# CATS-GS-GNSS.net
KiCad netlist of a schematic drawn in Altium Designer
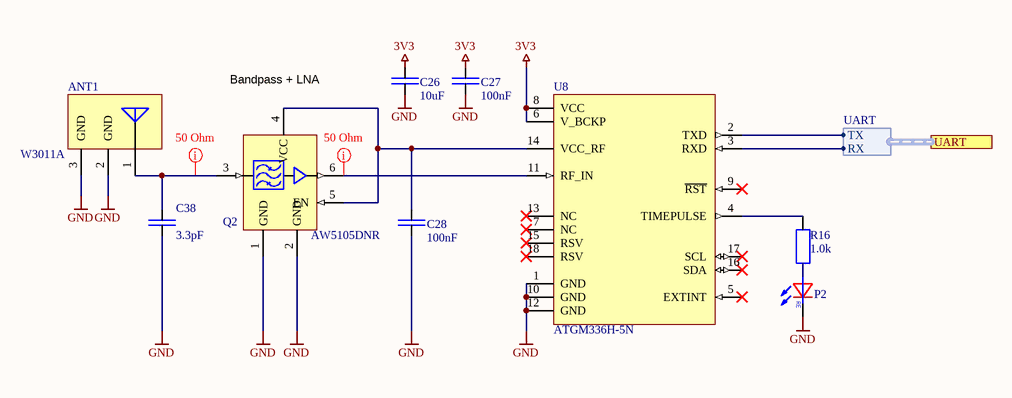
[diagram p0: CATS-GS-GNSS.SchDoc]

(export (version "E")
  (design (tool "Eeschema 10.0.6"))
  (components
    (comp (ref "ANT1")
      (value "W3011A")
      (footprint "SMD Antenna W3011A")
      (description "RF ANT 1.575GHZ CHIP SOLDER SMD")
      (libsource (lib "RF") (part "W3011A"))
    )
    (comp (ref "C26")
      (value "10uF")
      (footprint "SMD Keramikkondensator 0603")
      (description "SMD Ceramic Capacitor E6")
      (libsource (lib "Ceramic Capacitors-E6") (part "E6 - 10uF"))
    )
    (comp (ref "C27")
      (value "100nF")
      (footprint "SMD Keramikkondensator 0402")
      (description "SMD Ceramic Capacitor E6")
      (libsource (lib "CATS-EUROC") (part "E6 - 100nF"))
    )
    (comp (ref "C28")
      (value "100nF")
      (footprint "SMD Keramikkondensator 0402")
      (description "SMD Ceramic Capacitor E6")
      (libsource (lib "CATS-EUROC") (part "E6 - 100nF"))
    )
    (comp (ref "C38")
      (value "3.3pF")
      (footprint "SMD Keramikkondensator 0402")
      (description "SMD Ceramic Capacitor E6")
      (libsource (lib "Ceramic Capacitors-E6") (part "E6 - 3.3nF"))
    )
    (comp (ref "P2")
      (value "LED")
      (footprint "SMD LED 0603")
      (description "Color LED")
      (libsource (lib "Diodes") (part "LED"))
    )
    (comp (ref "Q2")
      (value "AW5105DNR")
      (footprint "SMD LNA AW5105DNR")
      (description "BDS/GPS/GNSS INTEGRATED FRONT-END MODULE WITH\r\nLOW NOISE AMPLIFIER AND FILTER")
      (libsource (lib "Analog") (part "AW5105DNR"))
    )
    (comp (ref "R16")
      (value "1.0k")
      (footprint "SMD Widerstand 0402")
      (description "SMD Chip Resistor E24")
      (libsource (lib "CATS-EUROC") (part "E24 - 1.0k"))
    )
    (comp (ref "U8")
      (value "ATGM336H-5N")
      (footprint "SMD MAX-8")
      (description "Chinese Crap GNSS Module")
      (libsource (lib "Sensors") (part "ATGM336H-5N"))
    )
  )
  (nets
    (net (code "2") (name "/RX") (class "Default")
      (node (ref "U8") (pin "3") (pinfunction "RXD_3") (pintype "input"))
    )
    (net (code "3") (name "/TX") (class "Default")
      (node (ref "U8") (pin "2") (pinfunction "TXD_2") (pintype "output"))
    )
    (net (code "5") (name "3V3") (class "Default")
      (node (ref "C26") (pin "2") (pinfunction "2_2") (pintype "passive"))
      (node (ref "C27") (pin "2") (pinfunction "2_2") (pintype "passive"))
      (node (ref "U8") (pin "6") (pinfunction "V_BCKP_6") (pintype "passive"))
      (node (ref "U8") (pin "8") (pinfunction "VCC_8") (pintype "passive"))
    )
    (net (code "6") (name "GND") (class "Default")
      (node (ref "ANT1") (pin "2") (pinfunction "GND_2") (pintype "passive"))
      (node (ref "ANT1") (pin "3") (pinfunction "GND_3") (pintype "passive"))
      (node (ref "C26") (pin "1") (pinfunction "1_1") (pintype "passive"))
      (node (ref "C27") (pin "1") (pinfunction "1_1") (pintype "passive"))
      (node (ref "C28") (pin "1") (pinfunction "1_1") (pintype "passive"))
      (node (ref "C38") (pin "1") (pinfunction "1_1") (pintype "passive"))
      (node (ref "P2") (pin "K") (pinfunction "K_K") (pintype "passive"))
      (node (ref "Q2") (pin "1") (pinfunction "GND_1") (pintype "passive"))
      (node (ref "Q2") (pin "2") (pinfunction "GND_2") (pintype "passive"))
      (node (ref "U8") (pin "1") (pinfunction "GND_1") (pintype "passive"))
      (node (ref "U8") (pin "10") (pinfunction "GND_10") (pintype "passive"))
      (node (ref "U8") (pin "12") (pinfunction "GND_12") (pintype "passive"))
    )
    (net (code "7") (name "Net-(ANT1-Pad1)_1") (class "Default")
      (node (ref "ANT1") (pin "1") (pinfunction "1_1") (pintype "passive"))
      (node (ref "C38") (pin "2") (pinfunction "2_2") (pintype "passive"))
      (node (ref "Q2") (pin "3") (pinfunction "3_3") (pintype "input"))
    )
    (net (code "8") (name "Net-(P2-PadA)") (class "Default")
      (node (ref "P2") (pin "A") (pinfunction "A_A") (pintype "passive"))
      (node (ref "R16") (pin "1") (pinfunction "1_1") (pintype "passive"))
    )
    (net (code "9") (name "Net-(Q2-VCC)") (class "Default")
      (node (ref "C28") (pin "2") (pinfunction "2_2") (pintype "passive"))
      (node (ref "Q2") (pin "4") (pinfunction "VCC_4") (pintype "passive"))
      (node (ref "Q2") (pin "5") (pinfunction "EN_5") (pintype "input"))
      (node (ref "U8") (pin "14") (pinfunction "VCC_RF_14") (pintype "passive"))
    )
    (net (code "10") (name "Net-(U8-RF_IN)") (class "Default")
      (node (ref "Q2") (pin "6") (pinfunction "EN_6") (pintype "output"))
      (node (ref "U8") (pin "11") (pinfunction "RF_IN_11") (pintype "input"))
    )
    (net (code "11") (name "Net-(U8-TIMEPULSE)") (class "Default")
      (node (ref "R16") (pin "2") (pinfunction "2_2") (pintype "passive"))
      (node (ref "U8") (pin "4") (pinfunction "TIMEPULSE_4") (pintype "output"))
    )
    (net (code "12") (name "unconnected-(ANT1-Pad1)") (class "Default")
      (node (ref "ANT1") (pin "1") (pinfunction "1_1") (pintype "passive"))
    )
    (net (code "13") (name "unconnected-(U8-EXTINT-Pad5)") (class "Default")
      (node (ref "U8") (pin "5") (pinfunction "EXTINT_5") (pintype "input+no_connect"))
    )
    (net (code "14") (name "unconnected-(U8-NC-Pad7)") (class "Default")
      (node (ref "U8") (pin "7") (pinfunction "NC_7") (pintype "passive+no_connect"))
    )
    (net (code "15") (name "unconnected-(U8-NC-Pad13)") (class "Default")
      (node (ref "U8") (pin "13") (pinfunction "NC_13") (pintype "passive+no_connect"))
    )
    (net (code "16") (name "unconnected-(U8-RSV-Pad15)") (class "Default")
      (node (ref "U8") (pin "15") (pinfunction "RSV_15") (pintype "passive+no_connect"))
    )
    (net (code "17") (name "unconnected-(U8-RSV-Pad18)") (class "Default")
      (node (ref "U8") (pin "18") (pinfunction "RSV_18") (pintype "passive+no_connect"))
    )
    (net (code "18") (name "unconnected-(U8-SCL-Pad17)") (class "Default")
      (node (ref "U8") (pin "17") (pinfunction "SCL_17") (pintype "bidirectional+no_connect"))
    )
    (net (code "19") (name "unconnected-(U8-SDA-Pad16)") (class "Default")
      (node (ref "U8") (pin "16") (pinfunction "SDA_16") (pintype "bidirectional+no_connect"))
    )
    (net (code "20") (name "unconnected-(U8-~{RST}-Pad9)") (class "Default")
      (node (ref "U8") (pin "9") (pinfunction "~{RST}_9") (pintype "input+no_connect"))
    )
  )
)
